# RC_Engine_Sound_ESP32.net
KiCad netlist of a schematic drawn in EAGLE
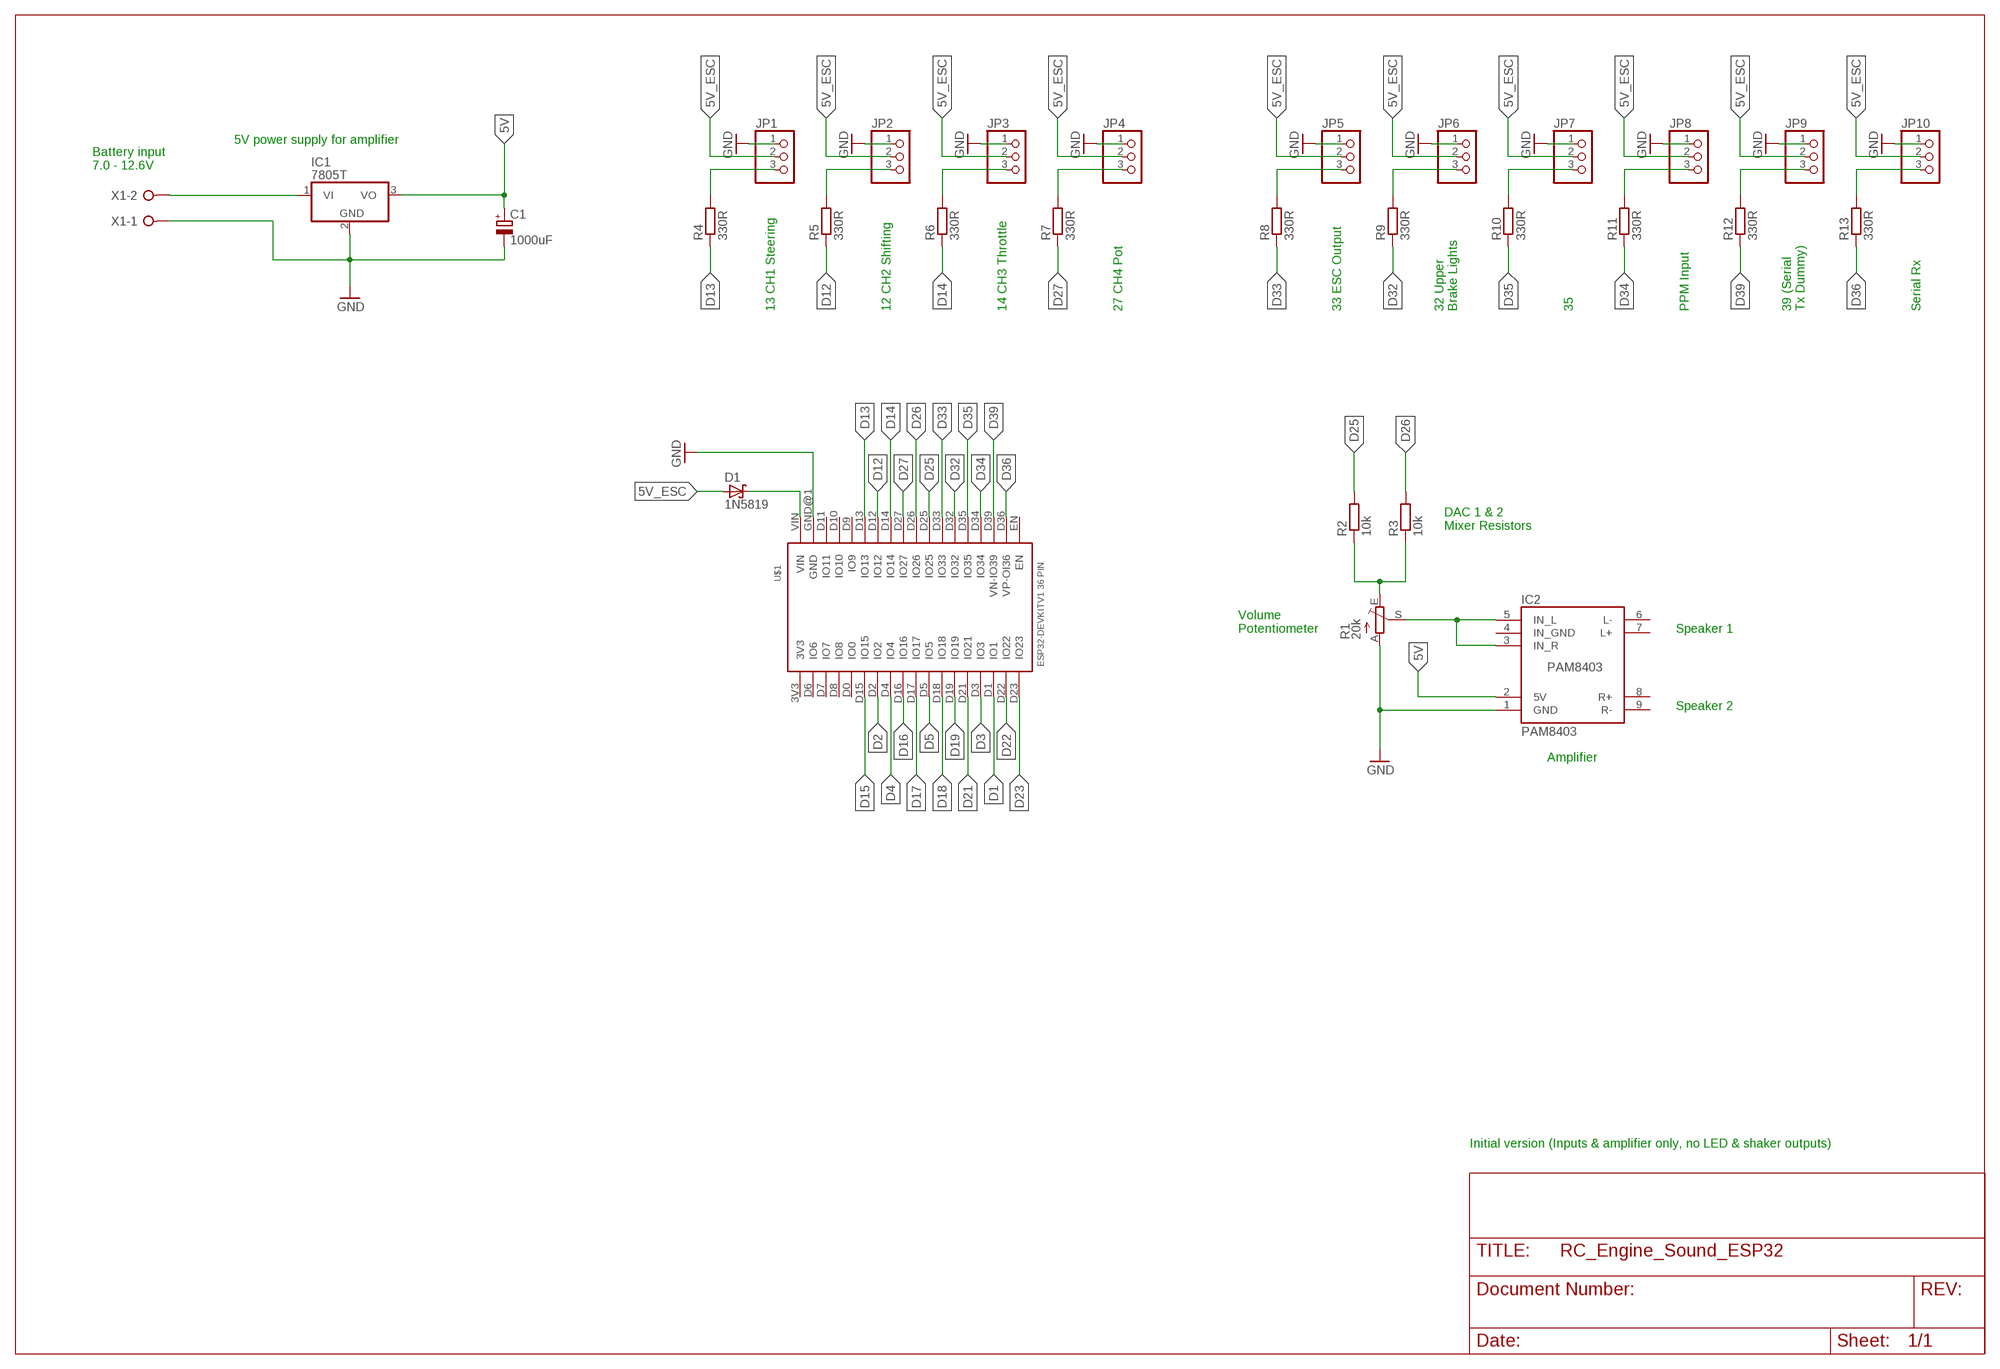
[diagram p0: schematic, sheet 1]

(export (version "E")
  (design (tool "Eeschema 10.0.6"))
  (components
    (comp (ref "C1")
      (value "1000uF")
      (footprint "eagle-import:E5-10,5")
      (libsource (lib "eagle-import") (part "CPOL-EUE5-10.5"))
    )
    (comp (ref "D1")
      (value "1N5819")
      (footprint "eagle-import:DO35-7")
      (libsource (lib "eagle-import") (part "SCHOTTKY-DIODEDO35-7"))
    )
    (comp (ref "IC1")
      (value "7805T")
      (footprint "eagle-import:TO220H")
      (libsource (lib "eagle-import") (part "78T05"))
    )
    (comp (ref "IC2")
      (value "PAM8403")
      (footprint "eagle-import:PAM8403")
      (libsource (lib "eagle-import") (part "PAM8403"))
    )
    (comp (ref "JP1")
      (value "PINHD-1X3")
      (footprint "eagle-import:1X03")
      (libsource (lib "eagle-import") (part "PINHD-1X3"))
    )
    (comp (ref "JP2")
      (value "PINHD-1X3")
      (footprint "eagle-import:1X03")
      (libsource (lib "eagle-import") (part "PINHD-1X3"))
    )
    (comp (ref "JP3")
      (value "PINHD-1X3")
      (footprint "eagle-import:1X03")
      (libsource (lib "eagle-import") (part "PINHD-1X3"))
    )
    (comp (ref "JP4")
      (value "PINHD-1X3")
      (footprint "eagle-import:1X03")
      (libsource (lib "eagle-import") (part "PINHD-1X3"))
    )
    (comp (ref "JP5")
      (value "PINHD-1X3")
      (footprint "eagle-import:1X03")
      (libsource (lib "eagle-import") (part "PINHD-1X3"))
    )
    (comp (ref "JP6")
      (value "PINHD-1X3")
      (footprint "eagle-import:1X03")
      (libsource (lib "eagle-import") (part "PINHD-1X3"))
    )
    (comp (ref "JP7")
      (value "PINHD-1X3")
      (footprint "eagle-import:1X03")
      (libsource (lib "eagle-import") (part "PINHD-1X3"))
    )
    (comp (ref "JP8")
      (value "PINHD-1X3")
      (footprint "eagle-import:1X03")
      (libsource (lib "eagle-import") (part "PINHD-1X3"))
    )
    (comp (ref "JP9")
      (value "PINHD-1X3")
      (footprint "eagle-import:1X03")
      (libsource (lib "eagle-import") (part "PINHD-1X3"))
    )
    (comp (ref "JP10")
      (value "PINHD-1X3")
      (footprint "eagle-import:1X03")
      (libsource (lib "eagle-import") (part "PINHD-1X3"))
    )
    (comp (ref "R1")
      (value "20k")
      (footprint "eagle-import:S64W")
      (libsource (lib "eagle-import") (part "TRIM_EU-S64W"))
    )
    (comp (ref "R2")
      (value "10k")
      (footprint "eagle-import:0207_10")
      (libsource (lib "eagle-import") (part "R-EU_0207/10"))
    )
    (comp (ref "R3")
      (value "10k")
      (footprint "eagle-import:0207_10")
      (libsource (lib "eagle-import") (part "R-EU_0207/10"))
    )
    (comp (ref "R4")
      (value "330R")
      (footprint "eagle-import:0207_2V")
      (libsource (lib "eagle-import") (part "R-EU_0207/2V"))
    )
    (comp (ref "R5")
      (value "330R")
      (footprint "eagle-import:0207_2V")
      (libsource (lib "eagle-import") (part "R-EU_0207/2V"))
    )
    (comp (ref "R6")
      (value "330R")
      (footprint "eagle-import:0207_2V")
      (libsource (lib "eagle-import") (part "R-EU_0207/2V"))
    )
    (comp (ref "R7")
      (value "330R")
      (footprint "eagle-import:0207_2V")
      (libsource (lib "eagle-import") (part "R-EU_0207/2V"))
    )
    (comp (ref "R8")
      (value "330R")
      (footprint "eagle-import:0207_2V")
      (libsource (lib "eagle-import") (part "R-EU_0207/2V"))
    )
    (comp (ref "R9")
      (value "330R")
      (footprint "eagle-import:0207_2V")
      (libsource (lib "eagle-import") (part "R-EU_0207/2V"))
    )
    (comp (ref "R10")
      (value "330R")
      (footprint "eagle-import:0207_2V")
      (libsource (lib "eagle-import") (part "R-EU_0207/2V"))
    )
    (comp (ref "R11")
      (value "330R")
      (footprint "eagle-import:0207_2V")
      (libsource (lib "eagle-import") (part "R-EU_0207/2V"))
    )
    (comp (ref "R12")
      (value "330R")
      (footprint "eagle-import:0207_2V")
      (libsource (lib "eagle-import") (part "R-EU_0207/2V"))
    )
    (comp (ref "R13")
      (value "330R")
      (footprint "eagle-import:0207_2V")
      (libsource (lib "eagle-import") (part "R-EU_0207/2V"))
    )
    (comp (ref "U$1")
      (value "ESP32DEVKITV1")
      (footprint "eagle-import:ESP32-DEVKITV1")
      (libsource (lib "eagle-import") (part "ESP32DEVKITV1"))
    )
    (comp (ref "X1")
      (value "W237-02P")
      (footprint "eagle-import:W237-132")
      (libsource (lib "eagle-import") (part "W237-02P"))
    )
  )
  (nets
    (net (code "1") (name "5V") (class "Default")
      (node (ref "C1") (pin "+") (pinfunction "+_+") (pintype "passive"))
      (node (ref "IC1") (pin "3") (pinfunction "VO_3") (pintype "passive"))
      (node (ref "IC2") (pin "2") (pinfunction "5V_2") (pintype "input"))
    )
    (net (code "2") (name "5V_ESC") (class "Default")
      (node (ref "D1") (pin "A") (pinfunction "A_A") (pintype "passive"))
      (node (ref "JP1") (pin "2") (pinfunction "2_2") (pintype "passive"))
      (node (ref "JP10") (pin "2") (pinfunction "2_2") (pintype "passive"))
      (node (ref "JP2") (pin "2") (pinfunction "2_2") (pintype "passive"))
      (node (ref "JP3") (pin "2") (pinfunction "2_2") (pintype "passive"))
      (node (ref "JP4") (pin "2") (pinfunction "2_2") (pintype "passive"))
      (node (ref "JP5") (pin "2") (pinfunction "2_2") (pintype "passive"))
      (node (ref "JP6") (pin "2") (pinfunction "2_2") (pintype "passive"))
      (node (ref "JP7") (pin "2") (pinfunction "2_2") (pintype "passive"))
      (node (ref "JP8") (pin "2") (pinfunction "2_2") (pintype "passive"))
      (node (ref "JP9") (pin "2") (pinfunction "2_2") (pintype "passive"))
    )
    (net (code "3") (name "D1") (class "Default")
      (node (ref "U$1") (pin "D1") (pinfunction "IO1_D1") (pintype "bidirectional"))
    )
    (net (code "4") (name "D2") (class "Default")
      (node (ref "U$1") (pin "D2") (pinfunction "IO2_D2") (pintype "bidirectional"))
    )
    (net (code "5") (name "D3") (class "Default")
      (node (ref "U$1") (pin "D3") (pinfunction "IO3_D3") (pintype "bidirectional"))
    )
    (net (code "6") (name "D4") (class "Default")
      (node (ref "U$1") (pin "D4") (pinfunction "IO4_D4") (pintype "bidirectional"))
    )
    (net (code "7") (name "D5") (class "Default")
      (node (ref "U$1") (pin "D5") (pinfunction "IO5_D5") (pintype "bidirectional"))
    )
    (net (code "8") (name "D12") (class "Default")
      (node (ref "R5") (pin "1") (pinfunction "1_1") (pintype "passive"))
      (node (ref "U$1") (pin "D12") (pinfunction "IO12_D12") (pintype "bidirectional"))
    )
    (net (code "9") (name "D13") (class "Default")
      (node (ref "R4") (pin "1") (pinfunction "1_1") (pintype "passive"))
      (node (ref "U$1") (pin "D13") (pinfunction "IO13_D13") (pintype "bidirectional"))
    )
    (net (code "10") (name "D14") (class "Default")
      (node (ref "R6") (pin "1") (pinfunction "1_1") (pintype "passive"))
      (node (ref "U$1") (pin "D14") (pinfunction "IO14_D14") (pintype "bidirectional"))
    )
    (net (code "11") (name "D15") (class "Default")
      (node (ref "U$1") (pin "D15") (pinfunction "IO15_D15") (pintype "bidirectional"))
    )
    (net (code "12") (name "D16") (class "Default")
      (node (ref "U$1") (pin "D16") (pinfunction "IO16_D16") (pintype "bidirectional"))
    )
    (net (code "13") (name "D17") (class "Default")
      (node (ref "U$1") (pin "D17") (pinfunction "IO17_D17") (pintype "bidirectional"))
    )
    (net (code "14") (name "D18") (class "Default")
      (node (ref "U$1") (pin "D18") (pinfunction "IO18_D18") (pintype "bidirectional"))
    )
    (net (code "15") (name "D19") (class "Default")
      (node (ref "U$1") (pin "D19") (pinfunction "IO19_D19") (pintype "bidirectional"))
    )
    (net (code "16") (name "D21") (class "Default")
      (node (ref "U$1") (pin "D21") (pinfunction "IO21_D21") (pintype "bidirectional"))
    )
    (net (code "17") (name "D22") (class "Default")
      (node (ref "U$1") (pin "D22") (pinfunction "IO22_D22") (pintype "bidirectional"))
    )
    (net (code "18") (name "D23") (class "Default")
      (node (ref "U$1") (pin "D23") (pinfunction "IO23_D23") (pintype "bidirectional"))
    )
    (net (code "19") (name "D25") (class "Default")
      (node (ref "R2") (pin "2") (pinfunction "2_2") (pintype "passive"))
      (node (ref "U$1") (pin "D25") (pinfunction "IO25_D25") (pintype "bidirectional"))
    )
    (net (code "20") (name "D26") (class "Default")
      (node (ref "R3") (pin "2") (pinfunction "2_2") (pintype "passive"))
      (node (ref "U$1") (pin "D26") (pinfunction "IO26_D26") (pintype "bidirectional"))
    )
    (net (code "21") (name "D27") (class "Default")
      (node (ref "R7") (pin "1") (pinfunction "1_1") (pintype "passive"))
      (node (ref "U$1") (pin "D27") (pinfunction "IO27_D27") (pintype "bidirectional"))
    )
    (net (code "22") (name "D32") (class "Default")
      (node (ref "R9") (pin "1") (pinfunction "1_1") (pintype "passive"))
      (node (ref "U$1") (pin "D32") (pinfunction "IO32_D32") (pintype "bidirectional"))
    )
    (net (code "23") (name "D33") (class "Default")
      (node (ref "R8") (pin "1") (pinfunction "1_1") (pintype "passive"))
      (node (ref "U$1") (pin "D33") (pinfunction "IO33_D33") (pintype "bidirectional"))
    )
    (net (code "24") (name "D34") (class "Default")
      (node (ref "R11") (pin "1") (pinfunction "1_1") (pintype "passive"))
      (node (ref "U$1") (pin "D34") (pinfunction "IO34_D34") (pintype "bidirectional"))
    )
    (net (code "25") (name "D35") (class "Default")
      (node (ref "R10") (pin "1") (pinfunction "1_1") (pintype "passive"))
      (node (ref "U$1") (pin "D35") (pinfunction "IO35_D35") (pintype "bidirectional"))
    )
    (net (code "26") (name "D36") (class "Default")
      (node (ref "R13") (pin "1") (pinfunction "1_1") (pintype "passive"))
      (node (ref "U$1") (pin "D36") (pinfunction "VP-OI36_D36") (pintype "bidirectional"))
    )
    (net (code "27") (name "D39") (class "Default")
      (node (ref "R12") (pin "1") (pinfunction "1_1") (pintype "passive"))
      (node (ref "U$1") (pin "D39") (pinfunction "VN-IO39_D39") (pintype "bidirectional"))
    )
    (net (code "28") (name "GND") (class "Default")
      (node (ref "C1") (pin "-") (pinfunction "-_-") (pintype "passive"))
      (node (ref "IC1") (pin "2") (pinfunction "GND_2") (pintype "passive"))
      (node (ref "IC2") (pin "1") (pinfunction "GND_1") (pintype "input"))
      (node (ref "JP1") (pin "1") (pinfunction "1_1") (pintype "passive"))
      (node (ref "JP10") (pin "1") (pinfunction "1_1") (pintype "passive"))
      (node (ref "JP2") (pin "1") (pinfunction "1_1") (pintype "passive"))
      (node (ref "JP3") (pin "1") (pinfunction "1_1") (pintype "passive"))
      (node (ref "JP4") (pin "1") (pinfunction "1_1") (pintype "passive"))
      (node (ref "JP5") (pin "1") (pinfunction "1_1") (pintype "passive"))
      (node (ref "JP6") (pin "1") (pinfunction "1_1") (pintype "passive"))
      (node (ref "JP7") (pin "1") (pinfunction "1_1") (pintype "passive"))
      (node (ref "JP8") (pin "1") (pinfunction "1_1") (pintype "passive"))
      (node (ref "JP9") (pin "1") (pinfunction "1_1") (pintype "passive"))
      (node (ref "R1") (pin "A") (pinfunction "A_A") (pintype "passive"))
      (node (ref "U$1") (pin "GND@1") (pinfunction "GND_GND@1") (pintype "bidirectional"))
      (node (ref "X1") (pin "1") (pinfunction "KL_1") (pintype "passive"))
    )
    (net (code "29") (name "Net-(D1-PadC)") (class "Default")
      (node (ref "D1") (pin "C") (pinfunction "C_C") (pintype "passive"))
      (node (ref "U$1") (pin "VIN") (pinfunction "VIN_VIN") (pintype "bidirectional"))
    )
    (net (code "30") (name "Net-(IC1-VI)") (class "Default")
      (node (ref "IC1") (pin "1") (pinfunction "VI_1") (pintype "input"))
      (node (ref "X1") (pin "2") (pinfunction "KL_2") (pintype "passive"))
    )
    (net (code "31") (name "Net-(IC2-IN_L)") (class "Default")
      (node (ref "IC2") (pin "3") (pinfunction "IN_R_3") (pintype "input"))
      (node (ref "IC2") (pin "5") (pinfunction "IN_L_5") (pintype "input"))
      (node (ref "R1") (pin "S") (pinfunction "S_S") (pintype "passive"))
    )
    (net (code "32") (name "Net-(JP1-Pad3)") (class "Default")
      (node (ref "JP1") (pin "3") (pinfunction "3_3") (pintype "passive"))
      (node (ref "R4") (pin "2") (pinfunction "2_2") (pintype "passive"))
    )
    (net (code "33") (name "Net-(JP2-Pad3)") (class "Default")
      (node (ref "JP2") (pin "3") (pinfunction "3_3") (pintype "passive"))
      (node (ref "R5") (pin "2") (pinfunction "2_2") (pintype "passive"))
    )
    (net (code "34") (name "Net-(JP3-Pad3)") (class "Default")
      (node (ref "JP3") (pin "3") (pinfunction "3_3") (pintype "passive"))
      (node (ref "R6") (pin "2") (pinfunction "2_2") (pintype "passive"))
    )
    (net (code "35") (name "Net-(JP4-Pad3)") (class "Default")
      (node (ref "JP4") (pin "3") (pinfunction "3_3") (pintype "passive"))
      (node (ref "R7") (pin "2") (pinfunction "2_2") (pintype "passive"))
    )
    (net (code "36") (name "Net-(JP5-Pad3)") (class "Default")
      (node (ref "JP5") (pin "3") (pinfunction "3_3") (pintype "passive"))
      (node (ref "R8") (pin "2") (pinfunction "2_2") (pintype "passive"))
    )
    (net (code "37") (name "Net-(JP6-Pad3)") (class "Default")
      (node (ref "JP6") (pin "3") (pinfunction "3_3") (pintype "passive"))
      (node (ref "R9") (pin "2") (pinfunction "2_2") (pintype "passive"))
    )
    (net (code "38") (name "Net-(JP7-Pad3)") (class "Default")
      (node (ref "JP7") (pin "3") (pinfunction "3_3") (pintype "passive"))
      (node (ref "R10") (pin "2") (pinfunction "2_2") (pintype "passive"))
    )
    (net (code "39") (name "Net-(JP8-Pad3)") (class "Default")
      (node (ref "JP8") (pin "3") (pinfunction "3_3") (pintype "passive"))
      (node (ref "R11") (pin "2") (pinfunction "2_2") (pintype "passive"))
    )
    (net (code "40") (name "Net-(JP9-Pad3)") (class "Default")
      (node (ref "JP9") (pin "3") (pinfunction "3_3") (pintype "passive"))
      (node (ref "R12") (pin "2") (pinfunction "2_2") (pintype "passive"))
    )
    (net (code "41") (name "Net-(JP10-Pad3)") (class "Default")
      (node (ref "JP10") (pin "3") (pinfunction "3_3") (pintype "passive"))
      (node (ref "R13") (pin "2") (pinfunction "2_2") (pintype "passive"))
    )
    (net (code "42") (name "Net-(R1-PadE)") (class "Default")
      (node (ref "R1") (pin "E") (pinfunction "E_E") (pintype "passive"))
      (node (ref "R2") (pin "1") (pinfunction "1_1") (pintype "passive"))
      (node (ref "R3") (pin "1") (pinfunction "1_1") (pintype "passive"))
    )
    (net (code "43") (name "unconnected-(IC2-IN_GND-Pad4)") (class "Default")
      (node (ref "IC2") (pin "4") (pinfunction "IN_GND_4") (pintype "input"))
    )
    (net (code "44") (name "unconnected-(IC2-L+-Pad7)") (class "Default")
      (node (ref "IC2") (pin "7") (pinfunction "L+_7") (pintype "output"))
    )
    (net (code "45") (name "unconnected-(IC2-L--Pad6)") (class "Default")
      (node (ref "IC2") (pin "6") (pinfunction "L-_6") (pintype "output"))
    )
    (net (code "46") (name "unconnected-(IC2-R+-Pad8)") (class "Default")
      (node (ref "IC2") (pin "8") (pinfunction "R+_8") (pintype "output"))
    )
    (net (code "47") (name "unconnected-(IC2-R--Pad9)") (class "Default")
      (node (ref "IC2") (pin "9") (pinfunction "R-_9") (pintype "output"))
    )
    (net (code "48") (name "unconnected-(U$1-IO0-PadD0)") (class "Default")
      (node (ref "U$1") (pin "D0") (pinfunction "IO0_D0") (pintype "bidirectional"))
    )
    (net (code "49") (name "unconnected-(U$1-IO6-PadD6)") (class "Default")
      (node (ref "U$1") (pin "D6") (pinfunction "IO6_D6") (pintype "bidirectional"))
    )
    (net (code "50") (name "unconnected-(U$1-IO7-PadD7)") (class "Default")
      (node (ref "U$1") (pin "D7") (pinfunction "IO7_D7") (pintype "bidirectional"))
    )
    (net (code "51") (name "unconnected-(U$1-IO8-PadD8)") (class "Default")
      (node (ref "U$1") (pin "D8") (pinfunction "IO8_D8") (pintype "bidirectional"))
    )
    (net (code "52") (name "unconnected-(U$1-IO9-PadD9)") (class "Default")
      (node (ref "U$1") (pin "D9") (pinfunction "IO9_D9") (pintype "bidirectional"))
    )
    (net (code "53") (name "unconnected-(U$1-IO10-PadD10)") (class "Default")
      (node (ref "U$1") (pin "D10") (pinfunction "IO10_D10") (pintype "bidirectional"))
    )
    (net (code "54") (name "unconnected-(U$1-IO11-PadD11)") (class "Default")
      (node (ref "U$1") (pin "D11") (pinfunction "IO11_D11") (pintype "bidirectional"))
    )
    (net (code "55") (name "unconnected-(U$1-Pad3V3)") (class "Default")
      (node (ref "U$1") (pin "3V3") (pinfunction "3V3_3V3") (pintype "bidirectional"))
    )
    (net (code "56") (name "unconnected-(U$1-PadEN)") (class "Default")
      (node (ref "U$1") (pin "EN") (pinfunction "EN_EN") (pintype "bidirectional"))
    )
  )
)
